# UART_Ctrl.net
KiCad netlist of a schematic drawn in Altium Designer
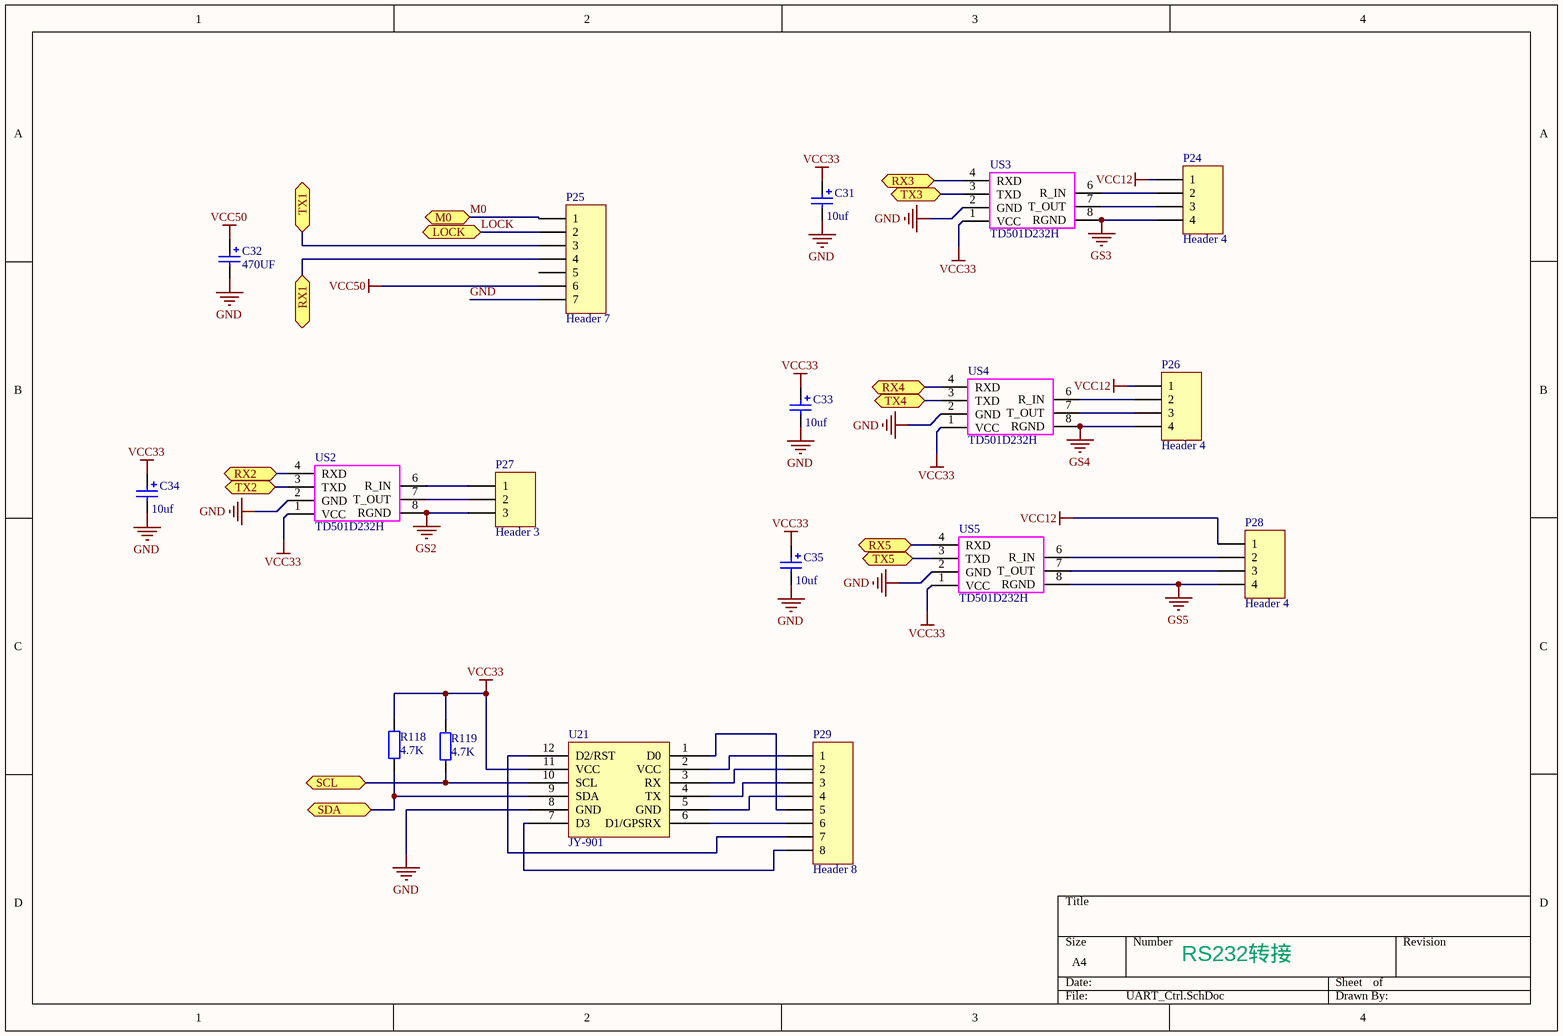
[diagram p0: UART_Ctrl.SchDoc]

(export (version "E")
  (design (tool "Eeschema 10.0.6"))
  (components
    (comp (ref "C31")
      (value "10uf")
      (footprint "C1206")
      (description "Polarized Capacitor (Axial)")
      (fields (field (name "Comment") "Cap Pol2") (field (name "PUBLISHER") "Altium Limited"))
      (libsource (lib "Miscellaneous Devices") (part "Cap Pol2"))
    )
    (comp (ref "C32")
      (value "470UF")
      (footprint "7243-D-TA")
      (description "Polarized Capacitor (Axial)")
      (fields (field (name "Comment") "Cap Pol2") (field (name "PUBLISHER") "Altium Limited"))
      (libsource (lib "Miscellaneous Devices") (part "Cap Pol2"))
    )
    (comp (ref "C33")
      (value "10uf")
      (footprint "C1206")
      (description "Polarized Capacitor (Axial)")
      (fields (field (name "Comment") "Cap Pol2") (field (name "PUBLISHER") "Altium Limited"))
      (libsource (lib "Miscellaneous Devices") (part "Cap Pol2"))
    )
    (comp (ref "C34")
      (value "10uf")
      (footprint "C1206")
      (description "Polarized Capacitor (Axial)")
      (fields (field (name "Comment") "Cap Pol2") (field (name "PUBLISHER") "Altium Limited"))
      (libsource (lib "Miscellaneous Devices") (part "Cap Pol2"))
    )
    (comp (ref "C35")
      (value "10uf")
      (footprint "C1206")
      (description "Polarized Capacitor (Axial)")
      (fields (field (name "Comment") "Cap Pol2") (field (name "PUBLISHER") "Altium Limited"))
      (libsource (lib "Miscellaneous Devices") (part "Cap Pol2"))
    )
    (comp (ref "P24")
      (value "Header 4")
      (footprint "3.81-4P")
      (description "Header, 4-Pin")
      (fields (field (name "PUBLISHER") "Altium Limited"))
      (libsource (lib "Miscellaneous Connectors") (part "Header 4"))
    )
    (comp (ref "P25")
      (value "Header 7")
      (footprint "HDR1X7")
      (description "Header, 7-Pin")
      (fields (field (name "PUBLISHER") "Altium Limited"))
      (libsource (lib "Miscellaneous Connectors") (part "Header 7"))
    )
    (comp (ref "P26")
      (value "Header 4")
      (footprint "3.81-4P")
      (description "Header, 4-Pin")
      (fields (field (name "PUBLISHER") "Altium Limited"))
      (libsource (lib "Miscellaneous Connectors") (part "Header 4"))
    )
    (comp (ref "P27")
      (value "Header 3")
      (footprint "381-3")
      (description "Header, 3-Pin")
      (fields (field (name "PUBLISHER") "Altium Limited"))
      (libsource (lib "Miscellaneous Connectors") (part "Header 3"))
    )
    (comp (ref "P28")
      (value "Header 4")
      (footprint "3.81-4P")
      (description "Header, 4-Pin")
      (fields (field (name "PUBLISHER") "Altium Limited"))
      (libsource (lib "Miscellaneous Connectors") (part "Header 4"))
    )
    (comp (ref "P29")
      (value "Header 8")
      (footprint "HDR1X8")
      (description "Header, 8-Pin")
      (fields (field (name "PUBLISHER") "Altium Limited"))
      (libsource (lib "Miscellaneous Connectors") (part "Header 8"))
    )
    (comp (ref "R118")
      (value "4.7K")
      (footprint "R1206")
      (description "Resistor")
      (fields (field (name "Comment") "Res2") (field (name "PUBLISHER") "Altium Limited"))
      (libsource (lib "Miscellaneous Devices") (part "Res2"))
    )
    (comp (ref "R119")
      (value "4.7K")
      (footprint "R1206")
      (description "Resistor")
      (fields (field (name "Comment") "Res2") (field (name "PUBLISHER") "Altium Limited"))
      (libsource (lib "Miscellaneous Devices") (part "Res2"))
    )
    (comp (ref "U21")
      (value "JY-901")
      (footprint "JY-901")
      (description "君悦智控高精度9轴传感器")
      (libsource (lib "JYModule") (part "JY-901"))
    )
    (comp (ref "US2")
      (value "TD501D232H")
      (footprint "TD501D232H")
      (libsource (lib "TD501D232H") (part "TD501D232H"))
    )
    (comp (ref "US3")
      (value "TD501D232H")
      (footprint "TD501D232H")
      (libsource (lib "TD501D232H") (part "TD501D232H"))
    )
    (comp (ref "US4")
      (value "TD501D232H")
      (footprint "TD501D232H")
      (libsource (lib "TD501D232H") (part "TD501D232H"))
    )
    (comp (ref "US5")
      (value "TD501D232H")
      (footprint "TD501D232H")
      (libsource (lib "TD501D232H") (part "TD501D232H"))
    )
  )
  (nets
    (net (code "1") (name "/LOCK") (class "Default")
      (node (ref "P25") (pin "2") (pinfunction "2_2") (pintype "passive"))
    )
    (net (code "2") (name "/M0") (class "Default")
      (node (ref "P25") (pin "1") (pinfunction "1_1") (pintype "passive"))
    )
    (net (code "3") (name "/RX1") (class "Default")
      (node (ref "P25") (pin "4") (pinfunction "4_4") (pintype "passive"))
    )
    (net (code "4") (name "/RX2") (class "Default")
      (node (ref "US2") (pin "4") (pinfunction "RXD_4") (pintype "passive"))
    )
    (net (code "5") (name "/RX3") (class "Default")
      (node (ref "US3") (pin "4") (pinfunction "RXD_4") (pintype "passive"))
    )
    (net (code "6") (name "/RX4") (class "Default")
      (node (ref "US4") (pin "4") (pinfunction "RXD_4") (pintype "passive"))
    )
    (net (code "7") (name "/RX5") (class "Default")
      (node (ref "US5") (pin "4") (pinfunction "RXD_4") (pintype "passive"))
    )
    (net (code "8") (name "/SCL") (class "Default")
      (node (ref "R119") (pin "2") (pinfunction "2_2") (pintype "passive"))
      (node (ref "U21") (pin "10") (pinfunction "SCL_10") (pintype "passive"))
    )
    (net (code "9") (name "/SDA") (class "Default")
      (node (ref "R118") (pin "2") (pinfunction "2_2") (pintype "passive"))
      (node (ref "U21") (pin "9") (pinfunction "SDA_9") (pintype "passive"))
    )
    (net (code "10") (name "/TX1") (class "Default")
      (node (ref "P25") (pin "3") (pinfunction "3_3") (pintype "passive"))
    )
    (net (code "11") (name "/TX2") (class "Default")
      (node (ref "US2") (pin "3") (pinfunction "TXD_3") (pintype "passive"))
    )
    (net (code "12") (name "/TX3") (class "Default")
      (node (ref "US3") (pin "3") (pinfunction "TXD_3") (pintype "passive"))
    )
    (net (code "13") (name "/TX4") (class "Default")
      (node (ref "US4") (pin "3") (pinfunction "TXD_3") (pintype "passive"))
    )
    (net (code "14") (name "/TX5") (class "Default")
      (node (ref "US5") (pin "3") (pinfunction "TXD_3") (pintype "passive"))
    )
    (net (code "15") (name "GND") (class "Default")
      (node (ref "C31") (pin "2") (pinfunction "2_2") (pintype "passive"))
      (node (ref "C32") (pin "2") (pinfunction "2_2") (pintype "passive"))
      (node (ref "C33") (pin "2") (pinfunction "2_2") (pintype "passive"))
      (node (ref "C34") (pin "2") (pinfunction "2_2") (pintype "passive"))
      (node (ref "C35") (pin "2") (pinfunction "2_2") (pintype "passive"))
      (node (ref "P25") (pin "7") (pinfunction "7_7") (pintype "passive"))
      (node (ref "U21") (pin "8") (pinfunction "GND_8") (pintype "passive"))
      (node (ref "US2") (pin "2") (pinfunction "GND_2") (pintype "passive"))
      (node (ref "US3") (pin "2") (pinfunction "GND_2") (pintype "passive"))
      (node (ref "US4") (pin "2") (pinfunction "GND_2") (pintype "passive"))
      (node (ref "US5") (pin "2") (pinfunction "GND_2") (pintype "passive"))
    )
    (net (code "16") (name "GS2") (class "Default")
      (node (ref "P27") (pin "3") (pinfunction "3_3") (pintype "passive"))
      (node (ref "US2") (pin "8") (pinfunction "RGND_8") (pintype "passive"))
    )
    (net (code "17") (name "GS3") (class "Default")
      (node (ref "P24") (pin "4") (pinfunction "4_4") (pintype "passive"))
      (node (ref "US3") (pin "8") (pinfunction "RGND_8") (pintype "passive"))
    )
    (net (code "18") (name "GS4") (class "Default")
      (node (ref "P26") (pin "4") (pinfunction "4_4") (pintype "passive"))
      (node (ref "US4") (pin "8") (pinfunction "RGND_8") (pintype "passive"))
    )
    (net (code "19") (name "GS5") (class "Default")
      (node (ref "P28") (pin "4") (pinfunction "4_4") (pintype "passive"))
      (node (ref "US5") (pin "8") (pinfunction "RGND_8") (pintype "passive"))
    )
    (net (code "20") (name "Net-(P29-Pad1)") (class "Default")
      (node (ref "P29") (pin "1") (pinfunction "1_1") (pintype "passive"))
      (node (ref "U21") (pin "2") (pinfunction "VCC_2") (pintype "passive"))
    )
    (net (code "21") (name "Net-(P29-Pad4)") (class "Default")
      (node (ref "P29") (pin "4") (pinfunction "4_4") (pintype "passive"))
      (node (ref "U21") (pin "5") (pinfunction "GND_5") (pintype "passive"))
    )
    (net (code "22") (name "Net-(U21-D0)") (class "Default")
      (node (ref "P29") (pin "5") (pinfunction "5_5") (pintype "passive"))
      (node (ref "U21") (pin "1") (pinfunction "D0_1") (pintype "passive"))
    )
    (net (code "23") (name "Net-(U21-D1{slash}GPSRX)") (class "Default")
      (node (ref "P29") (pin "6") (pinfunction "6_6") (pintype "passive"))
      (node (ref "U21") (pin "6") (pinfunction "D1/GPSRX_6") (pintype "passive"))
    )
    (net (code "24") (name "Net-(U21-D2{slash}RST)") (class "Default")
      (node (ref "P29") (pin "7") (pinfunction "7_7") (pintype "passive"))
      (node (ref "U21") (pin "12") (pinfunction "D2/RST_12") (pintype "passive"))
    )
    (net (code "25") (name "Net-(U21-D3)") (class "Default")
      (node (ref "P29") (pin "8") (pinfunction "8_8") (pintype "passive"))
      (node (ref "U21") (pin "7") (pinfunction "D3_7") (pintype "passive"))
    )
    (net (code "26") (name "Net-(U21-RX)") (class "Default")
      (node (ref "P29") (pin "2") (pinfunction "2_2") (pintype "passive"))
      (node (ref "U21") (pin "3") (pinfunction "RX_3") (pintype "passive"))
    )
    (net (code "27") (name "Net-(U21-TX)") (class "Default")
      (node (ref "P29") (pin "3") (pinfunction "3_3") (pintype "passive"))
      (node (ref "U21") (pin "4") (pinfunction "TX_4") (pintype "passive"))
    )
    (net (code "28") (name "Net-(US2-R_IN)") (class "Default")
      (node (ref "P27") (pin "1") (pinfunction "1_1") (pintype "passive"))
      (node (ref "US2") (pin "6") (pinfunction "R_IN_6") (pintype "passive"))
    )
    (net (code "29") (name "Net-(US2-T_OUT)") (class "Default")
      (node (ref "P27") (pin "2") (pinfunction "2_2") (pintype "passive"))
      (node (ref "US2") (pin "7") (pinfunction "T_OUT_7") (pintype "passive"))
    )
    (net (code "30") (name "Net-(US3-R_IN)") (class "Default")
      (node (ref "P24") (pin "2") (pinfunction "2_2") (pintype "passive"))
      (node (ref "US3") (pin "6") (pinfunction "R_IN_6") (pintype "passive"))
    )
    (net (code "31") (name "Net-(US3-T_OUT)") (class "Default")
      (node (ref "P24") (pin "3") (pinfunction "3_3") (pintype "passive"))
      (node (ref "US3") (pin "7") (pinfunction "T_OUT_7") (pintype "passive"))
    )
    (net (code "32") (name "Net-(US4-R_IN)") (class "Default")
      (node (ref "P26") (pin "2") (pinfunction "2_2") (pintype "passive"))
      (node (ref "US4") (pin "6") (pinfunction "R_IN_6") (pintype "passive"))
    )
    (net (code "33") (name "Net-(US4-T_OUT)") (class "Default")
      (node (ref "P26") (pin "3") (pinfunction "3_3") (pintype "passive"))
      (node (ref "US4") (pin "7") (pinfunction "T_OUT_7") (pintype "passive"))
    )
    (net (code "34") (name "Net-(US5-R_IN)") (class "Default")
      (node (ref "P28") (pin "2") (pinfunction "2_2") (pintype "passive"))
      (node (ref "US5") (pin "6") (pinfunction "R_IN_6") (pintype "passive"))
    )
    (net (code "35") (name "Net-(US5-T_OUT)") (class "Default")
      (node (ref "P28") (pin "3") (pinfunction "3_3") (pintype "passive"))
      (node (ref "US5") (pin "7") (pinfunction "T_OUT_7") (pintype "passive"))
    )
    (net (code "36") (name "VCC12") (class "Default")
      (node (ref "P24") (pin "1") (pinfunction "1_1") (pintype "passive"))
      (node (ref "P26") (pin "1") (pinfunction "1_1") (pintype "passive"))
      (node (ref "P28") (pin "1") (pinfunction "1_1") (pintype "passive"))
    )
    (net (code "37") (name "VCC33") (class "Default")
      (node (ref "C31") (pin "1") (pinfunction "1_1") (pintype "passive"))
      (node (ref "C33") (pin "1") (pinfunction "1_1") (pintype "passive"))
      (node (ref "C34") (pin "1") (pinfunction "1_1") (pintype "passive"))
      (node (ref "C35") (pin "1") (pinfunction "1_1") (pintype "passive"))
      (node (ref "R118") (pin "1") (pinfunction "1_1") (pintype "passive"))
      (node (ref "R119") (pin "1") (pinfunction "1_1") (pintype "passive"))
      (node (ref "U21") (pin "11") (pinfunction "VCC_11") (pintype "passive"))
      (node (ref "US2") (pin "1") (pinfunction "VCC_1") (pintype "passive"))
      (node (ref "US3") (pin "1") (pinfunction "VCC_1") (pintype "passive"))
      (node (ref "US4") (pin "1") (pinfunction "VCC_1") (pintype "passive"))
      (node (ref "US5") (pin "1") (pinfunction "VCC_1") (pintype "passive"))
    )
    (net (code "38") (name "VCC50") (class "Default")
      (node (ref "C32") (pin "1") (pinfunction "1_1") (pintype "passive"))
      (node (ref "P25") (pin "6") (pinfunction "6_6") (pintype "passive"))
    )
    (net (code "39") (name "unconnected-(P25-Pad5)") (class "Default")
      (node (ref "P25") (pin "5") (pinfunction "5_5") (pintype "passive"))
    )
  )
)
